# MCU.net
KiCad netlist of a schematic drawn in EAGLE
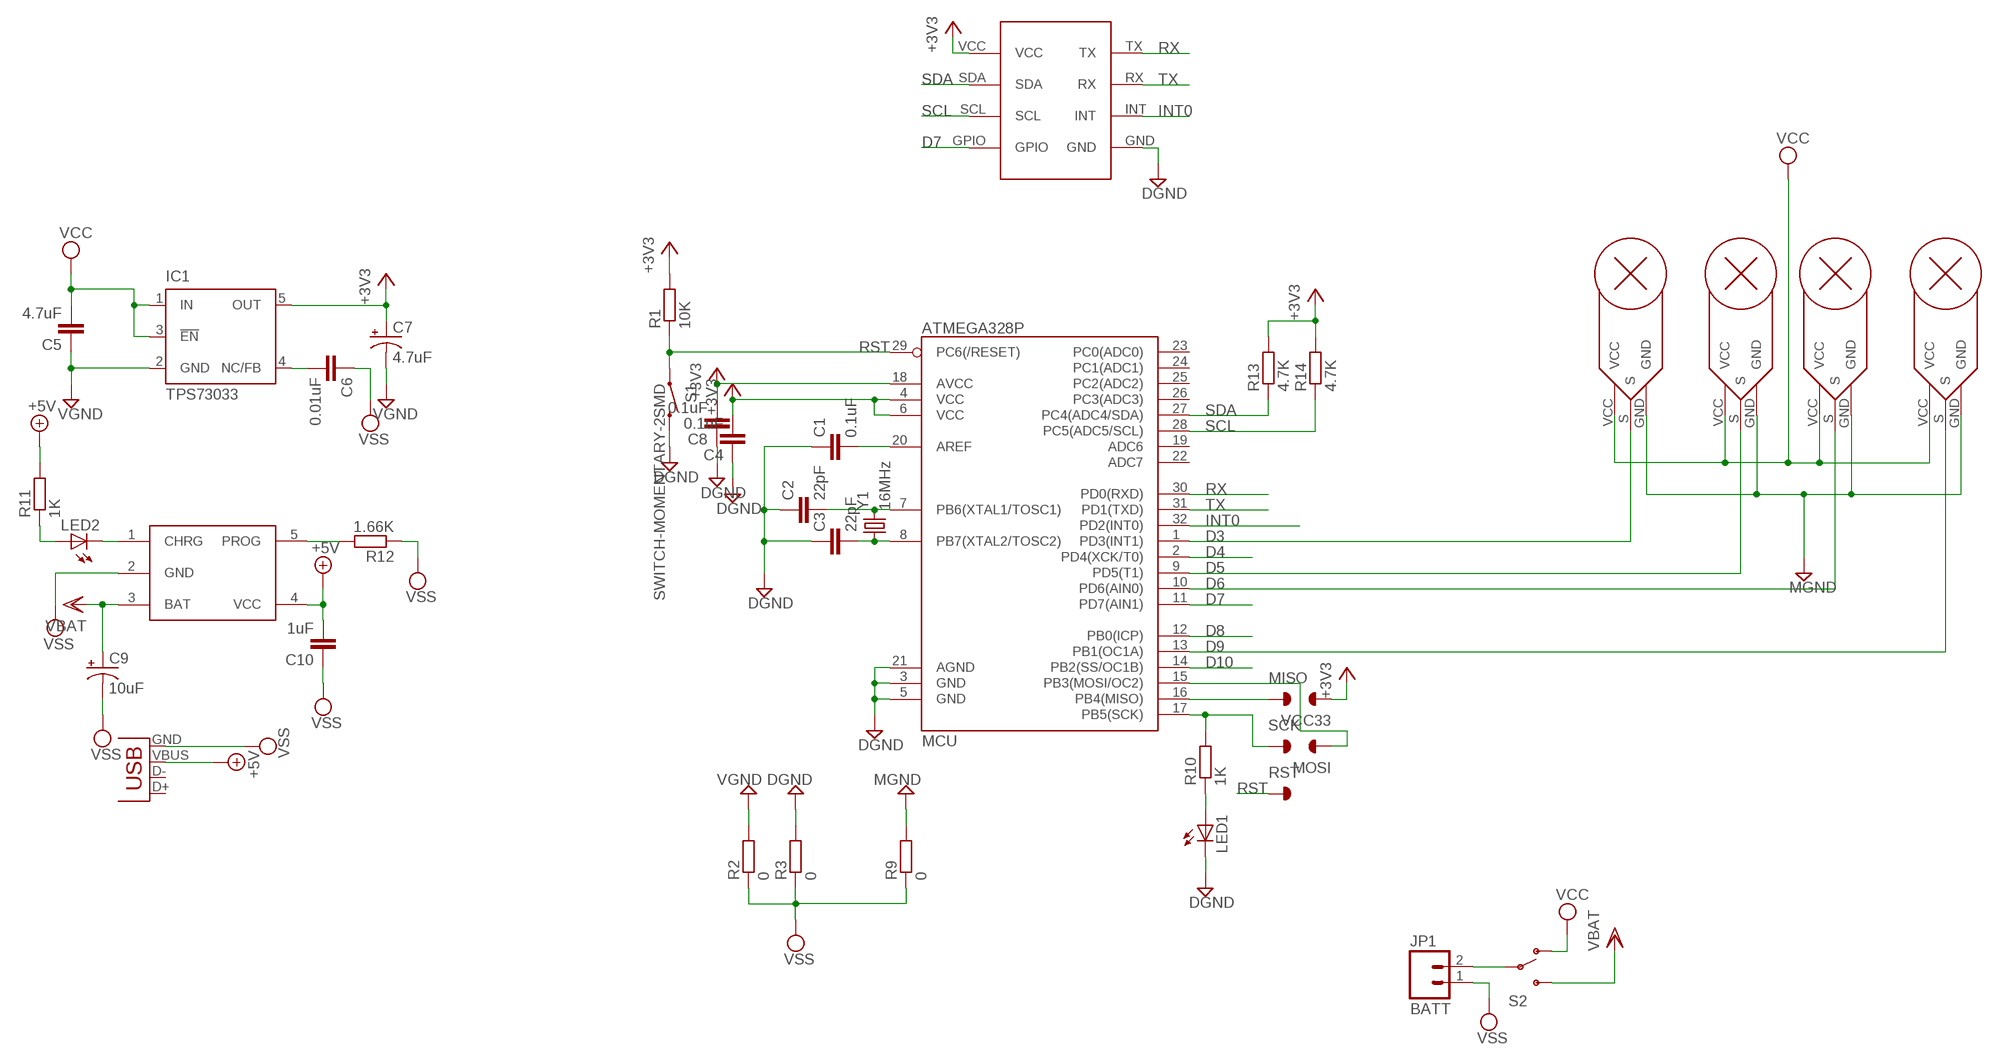
[diagram p0: schematic, sheet 1]

(export (version "E")
  (design (tool "Eeschema 10.0.6"))
  (components
    (comp (ref "C1")
      (value "0.1uF")
      (footprint "eagle-import:C0805")
      (libsource (lib "eagle-import") (part "C-EUC0805"))
    )
    (comp (ref "C2")
      (value "22pF")
      (footprint "eagle-import:C0603")
      (libsource (lib "eagle-import") (part "C-EUC0603"))
    )
    (comp (ref "C3")
      (value "22pF")
      (footprint "eagle-import:C0603")
      (libsource (lib "eagle-import") (part "C-EUC0603"))
    )
    (comp (ref "C4")
      (value "0.1uF")
      (footprint "eagle-import:C0805")
      (libsource (lib "eagle-import") (part "C-EUC0805"))
    )
    (comp (ref "C5")
      (value "4.7uF")
      (footprint "eagle-import:C0805")
      (libsource (lib "eagle-import") (part "C-EUC0805"))
    )
    (comp (ref "C6")
      (value "0.01uF")
      (footprint "eagle-import:C0805")
      (libsource (lib "eagle-import") (part "C-EUC0805"))
    )
    (comp (ref "C7")
      (value "4.7uF")
      (footprint "eagle-import:EIA3216")
      (libsource (lib "eagle-import") (part "CAP_POL1206"))
    )
    (comp (ref "C8")
      (value "0.1uF")
      (footprint "eagle-import:C0805")
      (libsource (lib "eagle-import") (part "C-EUC0805"))
    )
    (comp (ref "C9")
      (value "10uF")
      (footprint "eagle-import:EIA3216")
      (libsource (lib "eagle-import") (part "CAP_POL1206"))
    )
    (comp (ref "C10")
      (value "1uF")
      (footprint "eagle-import:C0805")
      (libsource (lib "eagle-import") (part "C-EUC0805"))
    )
    (comp (ref "IC1")
      (value "TPS73033")
      (footprint "eagle-import:SOT23-DBV")
      (fields (field (name "MF") "TEXAS INSTRUMENTS") (field (name "MPN") "TPS77033DBVT"))
      (libsource (lib "eagle-import") (part "TPS77033"))
    )
    (comp (ref "JP1")
      (value "BATT")
      (footprint "eagle-import:1X02")
      (libsource (lib "eagle-import") (part "M02PTH"))
    )
    (comp (ref "JP2")
      (value "USBSMD")
      (footprint "eagle-import:USB-MINIB")
      (libsource (lib "eagle-import") (part "USBSMD"))
    )
    (comp (ref "LED1")
      (value "LEDSML0805")
      (footprint "eagle-import:SML0805")
      (libsource (lib "eagle-import") (part "LEDSML0805"))
    )
    (comp (ref "LED2")
      (value "LEDSML0805")
      (footprint "eagle-import:SML0805")
      (libsource (lib "eagle-import") (part "LEDSML0805"))
    )
    (comp (ref "MCU")
      (value "ATMEGA328P")
      (footprint "eagle-import:TQFP32-08")
      (libsource (lib "eagle-import") (part "ATMEGA328_SMT"))
    )
    (comp (ref "MISO")
      (value "xx")
      (footprint "eagle-import:POINT")
      (libsource (lib "eagle-import") (part "POINT"))
    )
    (comp (ref "MOSI")
      (value "xx")
      (footprint "eagle-import:POINT")
      (libsource (lib "eagle-import") (part "POINT"))
    )
    (comp (ref "R1")
      (value "10K")
      (footprint "eagle-import:R0805")
      (libsource (lib "eagle-import") (part "R-EU_R0805"))
    )
    (comp (ref "R2")
      (value "0")
      (footprint "eagle-import:R0805")
      (libsource (lib "eagle-import") (part "R-EU_R0805"))
    )
    (comp (ref "R3")
      (value "0")
      (footprint "eagle-import:R0805")
      (libsource (lib "eagle-import") (part "R-EU_R0805"))
    )
    (comp (ref "R9")
      (value "0")
      (footprint "eagle-import:R0805")
      (libsource (lib "eagle-import") (part "R-EU_R0805"))
    )
    (comp (ref "R10")
      (value "1K")
      (footprint "eagle-import:R0805")
      (libsource (lib "eagle-import") (part "R-EU_R0805"))
    )
    (comp (ref "R11")
      (value "1K")
      (footprint "eagle-import:R0805")
      (libsource (lib "eagle-import") (part "R-EU_R0805"))
    )
    (comp (ref "R12")
      (value "1.66K")
      (footprint "eagle-import:R0805")
      (libsource (lib "eagle-import") (part "R-EU_R0805"))
    )
    (comp (ref "R13")
      (value "4.7K")
      (footprint "eagle-import:R0805")
      (libsource (lib "eagle-import") (part "R-EU_R0805"))
    )
    (comp (ref "R14")
      (value "4.7K")
      (footprint "eagle-import:R0805")
      (libsource (lib "eagle-import") (part "R-EU_R0805"))
    )
    (comp (ref "RST")
      (value "xx")
      (footprint "eagle-import:POINT")
      (libsource (lib "eagle-import") (part "POINT"))
    )
    (comp (ref "S1")
      (value "SWITCH-MOMENTARY-2SMD")
      (footprint "eagle-import:TACTILE_SWITCH_SMD")
      (libsource (lib "eagle-import") (part "SWITCH-MOMENTARY-2SMD"))
    )
    (comp (ref "S2")
      (value "SWITCH-SPDT-SMD-A")
      (footprint "eagle-import:SWITCH-SPST-SMD-A")
      (libsource (lib "eagle-import") (part "SWITCH-SPDT-SMD-A"))
    )
    (comp (ref "SCK")
      (value "xx")
      (footprint "eagle-import:POINT")
      (libsource (lib "eagle-import") (part "POINT"))
    )
    (comp (ref "U$1")
      (value "MOTOR-BOARDHOLDER")
      (footprint "eagle-import:MOTOR-HOLDER")
      (libsource (lib "eagle-import") (part "MOTOR-BOARDHOLDER"))
    )
    (comp (ref "U$2")
      (value "MOTOR-BOARDHOLDER")
      (footprint "eagle-import:MOTOR-HOLDER")
      (libsource (lib "eagle-import") (part "MOTOR-BOARDHOLDER"))
    )
    (comp (ref "U$3")
      (value "MOTOR-BOARDHOLDER")
      (footprint "eagle-import:MOTOR-HOLDER")
      (libsource (lib "eagle-import") (part "MOTOR-BOARDHOLDER"))
    )
    (comp (ref "U$4")
      (value "MOTOR-BOARDHOLDER")
      (footprint "eagle-import:MOTOR-HOLDER")
      (libsource (lib "eagle-import") (part "MOTOR-BOARDHOLDER"))
    )
    (comp (ref "U$5")
      (value "TP4055")
      (footprint "eagle-import:SOT23-5")
      (libsource (lib "eagle-import") (part "TP4055"))
    )
    (comp (ref "U$6")
      (value "BLUESENSORHOLDER")
      (footprint "eagle-import:BLUESENSOR-HOLDER")
      (libsource (lib "eagle-import") (part "BLUESENSORHOLDER"))
    )
    (comp (ref "VCC33")
      (value "xx")
      (footprint "eagle-import:POINT")
      (libsource (lib "eagle-import") (part "POINT"))
    )
    (comp (ref "Y1")
      (value "16MHz")
      (footprint "eagle-import:HC49US")
      (libsource (lib "eagle-import") (part "CRYSTALHC49US"))
    )
  )
  (nets
    (net (code "1") (name "+3V3") (class "Default")
      (node (ref "C4") (pin "2") (pinfunction "2_2") (pintype "passive"))
      (node (ref "C7") (pin "A") (pinfunction "+_A") (pintype "passive"))
      (node (ref "C8") (pin "2") (pinfunction "2_2") (pintype "passive"))
      (node (ref "IC1") (pin "5") (pinfunction "OUT_5") (pintype "passive"))
      (node (ref "MCU") (pin "18") (pinfunction "AVCC_18") (pintype "bidirectional"))
      (node (ref "MCU") (pin "4") (pinfunction "VCC_4") (pintype "bidirectional"))
      (node (ref "MCU") (pin "6") (pinfunction "VCC_6") (pintype "bidirectional"))
      (node (ref "R1") (pin "2") (pinfunction "2_2") (pintype "passive"))
      (node (ref "R13") (pin "2") (pinfunction "2_2") (pintype "passive"))
      (node (ref "R14") (pin "2") (pinfunction "2_2") (pintype "passive"))
      (node (ref "U$6") (pin "VCC") (pinfunction "VCC_VCC") (pintype "bidirectional"))
      (node (ref "VCC33") (pin "P$1") (pinfunction "1_P$1") (pintype "bidirectional"))
    )
    (net (code "2") (name "+5V") (class "Default")
      (node (ref "C10") (pin "2") (pinfunction "2_2") (pintype "passive"))
      (node (ref "JP2") (pin "VBUS") (pinfunction "VBUS_VBUS") (pintype "bidirectional"))
      (node (ref "R11") (pin "2") (pinfunction "2_2") (pintype "passive"))
      (node (ref "U$5") (pin "4") (pinfunction "VCC_4") (pintype "bidirectional"))
    )
    (net (code "3") (name "/D3") (class "Default")
      (node (ref "MCU") (pin "1") (pinfunction "PD3(INT1)_1") (pintype "bidirectional"))
      (node (ref "U$1") (pin "S") (pinfunction "S_S") (pintype "bidirectional"))
    )
    (net (code "4") (name "/D4") (class "Default")
      (node (ref "MCU") (pin "2") (pinfunction "PD4(XCK/T0)_2") (pintype "bidirectional"))
    )
    (net (code "5") (name "/D5") (class "Default")
      (node (ref "MCU") (pin "9") (pinfunction "PD5(T1)_9") (pintype "bidirectional"))
      (node (ref "U$2") (pin "S") (pinfunction "S_S") (pintype "bidirectional"))
    )
    (net (code "6") (name "/D6") (class "Default")
      (node (ref "MCU") (pin "10") (pinfunction "PD6(AIN0)_10") (pintype "bidirectional"))
      (node (ref "U$3") (pin "S") (pinfunction "S_S") (pintype "bidirectional"))
    )
    (net (code "7") (name "/D7") (class "Default")
      (node (ref "MCU") (pin "11") (pinfunction "PD7(AIN1)_11") (pintype "bidirectional"))
      (node (ref "U$6") (pin "GPIO") (pinfunction "GPIO_GPIO") (pintype "bidirectional"))
    )
    (net (code "8") (name "/D8") (class "Default")
      (node (ref "MCU") (pin "12") (pinfunction "PB0(ICP)_12") (pintype "bidirectional"))
    )
    (net (code "9") (name "/D9") (class "Default")
      (node (ref "MCU") (pin "13") (pinfunction "PB1(OC1A)_13") (pintype "bidirectional"))
      (node (ref "U$4") (pin "S") (pinfunction "S_S") (pintype "bidirectional"))
    )
    (net (code "10") (name "/D10") (class "Default")
      (node (ref "MCU") (pin "14") (pinfunction "PB2(SS/OC1B)_14") (pintype "bidirectional"))
    )
    (net (code "11") (name "/INT0") (class "Default")
      (node (ref "MCU") (pin "32") (pinfunction "PD2(INT0)_32") (pintype "bidirectional"))
      (node (ref "U$6") (pin "INT") (pinfunction "INT_INT") (pintype "bidirectional"))
    )
    (net (code "12") (name "/RST") (class "Default")
      (node (ref "MCU") (pin "29") (pinfunction "PC6(/RESET)_29") (pintype "bidirectional"))
      (node (ref "R1") (pin "1") (pinfunction "1_1") (pintype "passive"))
      (node (ref "RST") (pin "P$1") (pinfunction "1_P$1") (pintype "bidirectional"))
      (node (ref "S1") (pin "1") (pinfunction "1_1") (pintype "passive"))
    )
    (net (code "13") (name "/RX") (class "Default")
      (node (ref "MCU") (pin "30") (pinfunction "PD0(RXD)_30") (pintype "bidirectional"))
      (node (ref "U$6") (pin "TX") (pinfunction "TX_TX") (pintype "bidirectional"))
    )
    (net (code "14") (name "/SCL") (class "Default")
      (node (ref "MCU") (pin "28") (pinfunction "PC5(ADC5/SCL)_28") (pintype "bidirectional"))
      (node (ref "R14") (pin "1") (pinfunction "1_1") (pintype "passive"))
      (node (ref "U$6") (pin "SCL") (pinfunction "SCL_SCL") (pintype "bidirectional"))
    )
    (net (code "15") (name "/SDA") (class "Default")
      (node (ref "MCU") (pin "27") (pinfunction "PC4(ADC4/SDA)_27") (pintype "bidirectional"))
      (node (ref "R13") (pin "1") (pinfunction "1_1") (pintype "passive"))
      (node (ref "U$6") (pin "SDA") (pinfunction "SDA_SDA") (pintype "bidirectional"))
    )
    (net (code "16") (name "/TX") (class "Default")
      (node (ref "MCU") (pin "31") (pinfunction "PD1(TXD)_31") (pintype "bidirectional"))
      (node (ref "U$6") (pin "RX") (pinfunction "RX_RX") (pintype "bidirectional"))
    )
    (net (code "17") (name "DGND") (class "Default")
      (node (ref "C1") (pin "1") (pinfunction "1_1") (pintype "passive"))
      (node (ref "C2") (pin "1") (pinfunction "1_1") (pintype "passive"))
      (node (ref "C3") (pin "1") (pinfunction "1_1") (pintype "passive"))
      (node (ref "C4") (pin "1") (pinfunction "1_1") (pintype "passive"))
      (node (ref "C8") (pin "1") (pinfunction "1_1") (pintype "passive"))
      (node (ref "LED1") (pin "C") (pinfunction "C_C") (pintype "passive"))
      (node (ref "MCU") (pin "21") (pinfunction "AGND_21") (pintype "bidirectional"))
      (node (ref "MCU") (pin "3") (pinfunction "GND_3") (pintype "bidirectional"))
      (node (ref "MCU") (pin "5") (pinfunction "GND_5") (pintype "bidirectional"))
      (node (ref "R3") (pin "2") (pinfunction "2_2") (pintype "passive"))
      (node (ref "S1") (pin "3") (pinfunction "2_3") (pintype "passive"))
      (node (ref "U$6") (pin "GND") (pinfunction "GND_GND") (pintype "bidirectional"))
    )
    (net (code "18") (name "MGND") (class "Default")
      (node (ref "R9") (pin "2") (pinfunction "2_2") (pintype "passive"))
      (node (ref "U$1") (pin "GND") (pinfunction "GND_GND") (pintype "bidirectional"))
      (node (ref "U$2") (pin "GND") (pinfunction "GND_GND") (pintype "bidirectional"))
      (node (ref "U$3") (pin "GND") (pinfunction "GND_GND") (pintype "bidirectional"))
      (node (ref "U$4") (pin "GND") (pinfunction "GND_GND") (pintype "bidirectional"))
    )
    (net (code "19") (name "Net-(IC1-NC{slash}FB)") (class "Default")
      (node (ref "C6") (pin "2") (pinfunction "2_2") (pintype "passive"))
      (node (ref "IC1") (pin "4") (pinfunction "NC/FB_4") (pintype "passive"))
    )
    (net (code "20") (name "Net-(LED1-PadA)") (class "Default")
      (node (ref "LED1") (pin "A") (pinfunction "A_A") (pintype "passive"))
      (node (ref "R10") (pin "1") (pinfunction "1_1") (pintype "passive"))
    )
    (net (code "21") (name "Net-(LED2-PadA)") (class "Default")
      (node (ref "LED2") (pin "A") (pinfunction "A_A") (pintype "passive"))
      (node (ref "R11") (pin "1") (pinfunction "1_1") (pintype "passive"))
    )
    (net (code "22") (name "Net-(MCU-AREF)") (class "Default")
      (node (ref "C1") (pin "2") (pinfunction "2_2") (pintype "passive"))
      (node (ref "MCU") (pin "20") (pinfunction "AREF_20") (pintype "bidirectional"))
    )
    (net (code "23") (name "Net-(MCU-PB3(MOSI{slash}OC2))") (class "Default")
      (node (ref "MCU") (pin "15") (pinfunction "PB3(MOSI/OC2)_15") (pintype "bidirectional"))
      (node (ref "MOSI") (pin "P$1") (pinfunction "1_P$1") (pintype "bidirectional"))
    )
    (net (code "24") (name "Net-(MCU-PB4(MISO))") (class "Default")
      (node (ref "MCU") (pin "16") (pinfunction "PB4(MISO)_16") (pintype "bidirectional"))
      (node (ref "MISO") (pin "P$1") (pinfunction "1_P$1") (pintype "bidirectional"))
    )
    (net (code "25") (name "Net-(MCU-PB5(SCK))") (class "Default")
      (node (ref "MCU") (pin "17") (pinfunction "PB5(SCK)_17") (pintype "bidirectional"))
      (node (ref "R10") (pin "2") (pinfunction "2_2") (pintype "passive"))
      (node (ref "SCK") (pin "P$1") (pinfunction "1_P$1") (pintype "bidirectional"))
    )
    (net (code "26") (name "Net-(MCU-PB6(XTAL1{slash}TOSC1))") (class "Default")
      (node (ref "C2") (pin "2") (pinfunction "2_2") (pintype "passive"))
      (node (ref "MCU") (pin "7") (pinfunction "PB6(XTAL1/TOSC1)_7") (pintype "bidirectional"))
      (node (ref "Y1") (pin "2") (pinfunction "2_2") (pintype "passive"))
    )
    (net (code "27") (name "Net-(MCU-PB7(XTAL2{slash}TOSC2))") (class "Default")
      (node (ref "C3") (pin "2") (pinfunction "2_2") (pintype "passive"))
      (node (ref "MCU") (pin "8") (pinfunction "PB7(XTAL2/TOSC2)_8") (pintype "bidirectional"))
      (node (ref "Y1") (pin "1") (pinfunction "1_1") (pintype "passive"))
    )
    (net (code "28") (name "Net-(S2-P)") (class "Default")
      (node (ref "JP1") (pin "2") (pinfunction "2_2") (pintype "passive"))
      (node (ref "S2") (pin "2") (pinfunction "P_2") (pintype "passive"))
    )
    (net (code "29") (name "Net-(U$5-CHRG)") (class "Default")
      (node (ref "LED2") (pin "C") (pinfunction "C_C") (pintype "passive"))
      (node (ref "U$5") (pin "1") (pinfunction "CHRG_1") (pintype "bidirectional"))
    )
    (net (code "30") (name "Net-(U$5-PROG)") (class "Default")
      (node (ref "R12") (pin "2") (pinfunction "2_2") (pintype "passive"))
      (node (ref "U$5") (pin "5") (pinfunction "PROG_5") (pintype "bidirectional"))
    )
    (net (code "31") (name "VBAT") (class "Default")
      (node (ref "C9") (pin "A") (pinfunction "+_A") (pintype "passive"))
      (node (ref "S2") (pin "3") (pinfunction "S_3") (pintype "passive"))
      (node (ref "U$5") (pin "3") (pinfunction "BAT_3") (pintype "bidirectional"))
    )
    (net (code "32") (name "VCC") (class "Default")
      (node (ref "C5") (pin "2") (pinfunction "2_2") (pintype "passive"))
      (node (ref "IC1") (pin "1") (pinfunction "IN_1") (pintype "input"))
      (node (ref "IC1") (pin "3") (pinfunction "~{EN}_3") (pintype "input"))
      (node (ref "S2") (pin "1") (pinfunction "O_1") (pintype "passive"))
      (node (ref "U$1") (pin "VCC") (pinfunction "VCC_VCC") (pintype "bidirectional"))
      (node (ref "U$2") (pin "VCC") (pinfunction "VCC_VCC") (pintype "bidirectional"))
      (node (ref "U$3") (pin "VCC") (pinfunction "VCC_VCC") (pintype "bidirectional"))
      (node (ref "U$4") (pin "VCC") (pinfunction "VCC_VCC") (pintype "bidirectional"))
    )
    (net (code "33") (name "VGND") (class "Default")
      (node (ref "C5") (pin "1") (pinfunction "1_1") (pintype "passive"))
      (node (ref "C7") (pin "C") (pinfunction "-_C") (pintype "passive"))
      (node (ref "IC1") (pin "2") (pinfunction "GND_2") (pintype "power_in"))
      (node (ref "R2") (pin "2") (pinfunction "2_2") (pintype "passive"))
    )
    (net (code "34") (name "VSS") (class "Default")
      (node (ref "C10") (pin "1") (pinfunction "1_1") (pintype "passive"))
      (node (ref "C6") (pin "1") (pinfunction "1_1") (pintype "passive"))
      (node (ref "C9") (pin "C") (pinfunction "-_C") (pintype "passive"))
      (node (ref "JP1") (pin "1") (pinfunction "1_1") (pintype "passive"))
      (node (ref "JP2") (pin "GND") (pinfunction "GND_GND") (pintype "bidirectional"))
      (node (ref "R12") (pin "1") (pinfunction "1_1") (pintype "passive"))
      (node (ref "R2") (pin "1") (pinfunction "1_1") (pintype "passive"))
      (node (ref "R3") (pin "1") (pinfunction "1_1") (pintype "passive"))
      (node (ref "R9") (pin "1") (pinfunction "1_1") (pintype "passive"))
      (node (ref "U$5") (pin "2") (pinfunction "GND_2") (pintype "bidirectional"))
    )
    (net (code "35") (name "unconnected-(JP2-PadD+)") (class "Default")
      (node (ref "JP2") (pin "D+") (pinfunction "D+_D+") (pintype "bidirectional"))
    )
    (net (code "36") (name "unconnected-(JP2-PadD-)") (class "Default")
      (node (ref "JP2") (pin "D-") (pinfunction "D-_D-") (pintype "bidirectional"))
    )
    (net (code "37") (name "unconnected-(MCU-ADC6-Pad19)") (class "Default")
      (node (ref "MCU") (pin "19") (pinfunction "ADC6_19") (pintype "bidirectional"))
    )
    (net (code "38") (name "unconnected-(MCU-ADC7-Pad22)") (class "Default")
      (node (ref "MCU") (pin "22") (pinfunction "ADC7_22") (pintype "bidirectional"))
    )
    (net (code "39") (name "unconnected-(MCU-PC0(ADC0)-Pad23)") (class "Default")
      (node (ref "MCU") (pin "23") (pinfunction "PC0(ADC0)_23") (pintype "bidirectional"))
    )
    (net (code "40") (name "unconnected-(MCU-PC1(ADC1)-Pad24)") (class "Default")
      (node (ref "MCU") (pin "24") (pinfunction "PC1(ADC1)_24") (pintype "bidirectional"))
    )
    (net (code "41") (name "unconnected-(MCU-PC2(ADC2)-Pad25)") (class "Default")
      (node (ref "MCU") (pin "25") (pinfunction "PC2(ADC2)_25") (pintype "bidirectional"))
    )
    (net (code "42") (name "unconnected-(MCU-PC3(ADC3)-Pad26)") (class "Default")
      (node (ref "MCU") (pin "26") (pinfunction "PC3(ADC3)_26") (pintype "bidirectional"))
    )
  )
)
